# efr32_general.net
KiCad netlist of a schematic drawn in Altium Designer
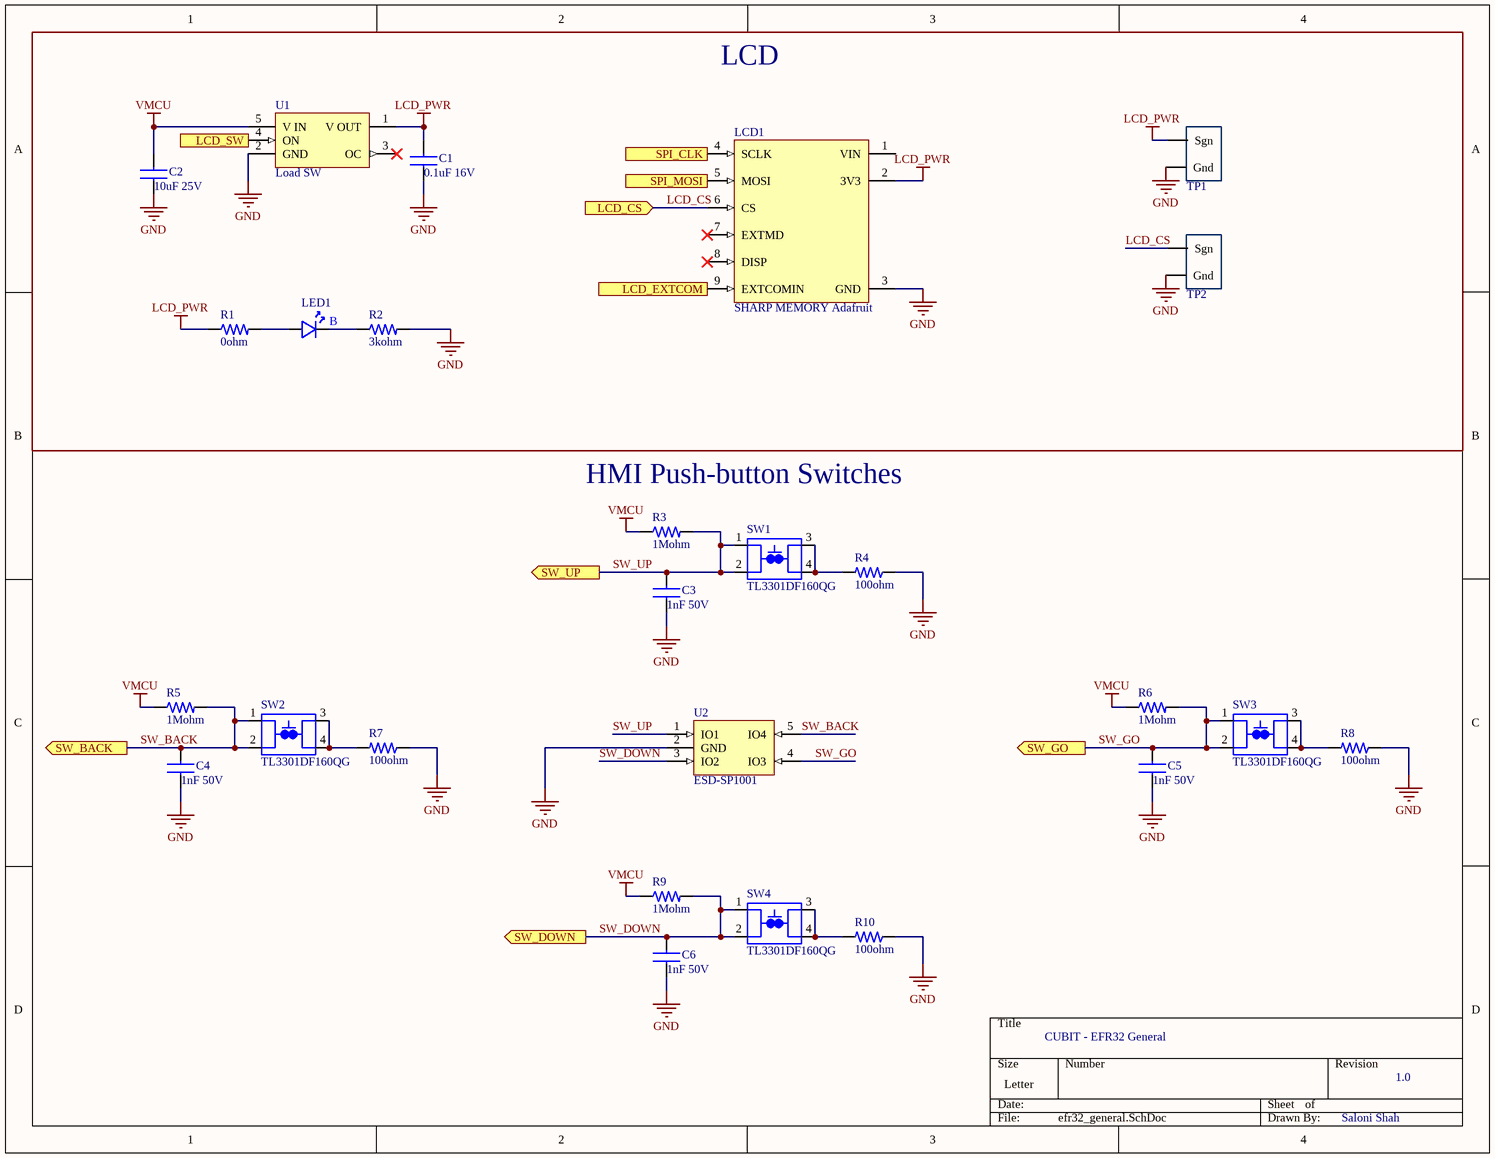
[diagram p0: efr32_general.SchDoc]

(export (version "E")
  (design (tool "Eeschema 10.0.6"))
  (components
    (comp (ref "C1")
      (value "0.1uF 16V")
      (footprint "CAP_0805_02X125")
      (description "Cap Ceramic 0.1uF 16V X7R 10% SMD 0805 125°C Paper T/R")
      (fields
        (field (name "MANUFACTURER") "KEMET")
        (field (name "MANUFACTURER PART NUMBER") "C0805C104K4RACAUTO")
      )
      (libsource (lib "LPEDT_proj_lib") (part "C0805C104K4RACAUTO"))
    )
    (comp (ref "C2")
      (value "10uF 25V")
      (footprint "CAP_0805_02X125")
      (description "Cap 0805 25 V 10 uF ±20% Tolerance X5R Monolithic Ceramic Chip Capacitor")
      (fields
        (field (name "MANUFACTURER") "Murata")
        (field (name "MANUFACTURER PART NUMBER") "GRM21BR61E106KA73K")
      )
      (libsource (lib "LPEDT_proj_lib") (part "GRM21BR61E106KA73K"))
    )
    (comp (ref "C3")
      (value "1nF 50V")
      (footprint "CAP_0805_02X125")
      (description "1nF ±10% 50V X7R 0805")
      (fields
        (field (name "MANUFACTURER") "Samsung")
        (field (name "MANUFACTURER PART NUMBER") "CL21B102KBANFNC")
      )
      (libsource (lib "LPEDT_proj_lib") (part "CL21B102KBANFNC"))
    )
    (comp (ref "C4")
      (value "1nF 50V")
      (footprint "CAP_0805_02X125")
      (description "1nF ±10% 50V X7R 0805")
      (fields
        (field (name "MANUFACTURER") "Samsung")
        (field (name "MANUFACTURER PART NUMBER") "CL21B102KBANFNC")
      )
      (libsource (lib "LPEDT_proj_lib") (part "CL21B102KBANFNC"))
    )
    (comp (ref "C5")
      (value "1nF 50V")
      (footprint "CAP_0805_02X125")
      (description "1nF ±10% 50V X7R 0805")
      (fields
        (field (name "MANUFACTURER") "Samsung")
        (field (name "MANUFACTURER PART NUMBER") "CL21B102KBANFNC")
      )
      (libsource (lib "LPEDT_proj_lib") (part "CL21B102KBANFNC"))
    )
    (comp (ref "C6")
      (value "1nF 50V")
      (footprint "CAP_0805_02X125")
      (description "1nF ±10% 50V X7R 0805")
      (fields
        (field (name "MANUFACTURER") "Samsung")
        (field (name "MANUFACTURER PART NUMBER") "CL21B102KBANFNC")
      )
      (libsource (lib "LPEDT_proj_lib") (part "CL21B102KBANFNC"))
    )
    (comp (ref "LCD1")
      (value "SHARP MEMORY Adafruit")
      (footprint "LCD_SHARP_MEMORY_9_PIN")
      (description "Conn AV RCA (Phono) Plug 2 Cont Sz 0.125\" Cbl Mnt Clamp Copper Alloy")
      (fields
        (field (name "MANUFACTURER") "Adafruit Industries")
        (field (name "MANUFACTURER PART NUMBER") "3502")
      )
      (libsource (lib "LPEDT_proj_lib") (part "3502"))
    )
    (comp (ref "LED1")
      (value "150060BS75000")
      (footprint "LED_0603_RED_WL-SMCW")
      (description "Led, Blue, 470 Nm, 3.2 V, 30 Ma, 145 Mcd Rohs Compliant: Yes")
      (fields (field (name "MANUFACTURER") "Wurth Electronics"))
      (libsource (lib "LPEDT_proj_lib") (part "150060BS75000"))
    )
    (comp (ref "R1")
      (value "0ohm")
      (footprint "CAP_0402_1mm")
      (description "Res 0 Ohms ±5% 0.063 W 0402 Thick Film Surface Mount Chip Resistor")
      (fields
        (field (name "MANUFACTURER") "Samsung")
        (field (name "MANUFACTURER PART NUMBER") "RC1005J000CS")
      )
      (libsource (lib "LPEDT_proj_lib") (part "RC1005J000CS"))
    )
    (comp (ref "R2")
      (value "3kohm")
      (footprint "CAP_0603_1MM")
      (description "Res 3000Ω ± 1.00% 0.1W ± 100ppm/℃ 0603")
      (fields
        (field (name "MANUFACTURER") "Yageo")
        (field (name "MANUFACTURER PART NUMBER") "RC0603FR-073KL")
      )
      (libsource (lib "LPEDT_proj_lib") (part "RC0603FR-073KL"))
    )
    (comp (ref "R3")
      (value "1Mohm")
      (footprint "2_Chip_0603_RMCF")
      (description "Res 1M Ohm 1% 1/10W ±100ppm/°C Molded SMD Paper T/R")
      (fields
        (field (name "MANUFACTURER") "Stackpole Electronics")
        (field (name "MANUFACTURER PART NUMBER") "RMCF0603FT1M00")
      )
      (libsource (lib "LPEDT_proj_lib") (part "RMCF0603FT1M00"))
    )
    (comp (ref "R4")
      (value "100ohm")
      (footprint "2_Chip_0603_RMCF")
      (description "Res 100 Ohm 1% 1/10W ±100ppm/°C Molded SMD SMD Paper T/R")
      (fields
        (field (name "MANUFACTURER") "Stackpole Electronics")
        (field (name "MANUFACTURER PART NUMBER") "RMCF0603FT100R")
      )
      (libsource (lib "LPEDT_proj_lib") (part "RMCF0603FT100R"))
    )
    (comp (ref "R5")
      (value "1Mohm")
      (footprint "2_Chip_0603_RMCF")
      (description "Res 1M Ohm 1% 1/10W ±100ppm/°C Molded SMD Paper T/R")
      (fields
        (field (name "MANUFACTURER") "Stackpole Electronics")
        (field (name "MANUFACTURER PART NUMBER") "RMCF0603FT1M00")
      )
      (libsource (lib "LPEDT_proj_lib") (part "RMCF0603FT1M00"))
    )
    (comp (ref "R6")
      (value "1Mohm")
      (footprint "2_Chip_0603_RMCF")
      (description "Res 1M Ohm 1% 1/10W ±100ppm/°C Molded SMD Paper T/R")
      (fields
        (field (name "MANUFACTURER") "Stackpole Electronics")
        (field (name "MANUFACTURER PART NUMBER") "RMCF0603FT1M00")
      )
      (libsource (lib "LPEDT_proj_lib") (part "RMCF0603FT1M00"))
    )
    (comp (ref "R7")
      (value "100ohm")
      (footprint "2_Chip_0603_RMCF")
      (description "Res 100 Ohm 1% 1/10W ±100ppm/°C Molded SMD SMD Paper T/R")
      (fields
        (field (name "MANUFACTURER") "Stackpole Electronics")
        (field (name "MANUFACTURER PART NUMBER") "RMCF0603FT100R")
      )
      (libsource (lib "LPEDT_proj_lib") (part "RMCF0603FT100R"))
    )
    (comp (ref "R8")
      (value "100ohm")
      (footprint "2_Chip_0603_RMCF")
      (description "Res 100 Ohm 1% 1/10W ±100ppm/°C Molded SMD SMD Paper T/R")
      (fields
        (field (name "MANUFACTURER") "Stackpole Electronics")
        (field (name "MANUFACTURER PART NUMBER") "RMCF0603FT100R")
      )
      (libsource (lib "LPEDT_proj_lib") (part "RMCF0603FT100R"))
    )
    (comp (ref "R9")
      (value "1Mohm")
      (footprint "2_Chip_0603_RMCF")
      (description "Res 1M Ohm 1% 1/10W ±100ppm/°C Molded SMD Paper T/R")
      (fields
        (field (name "MANUFACTURER") "Stackpole Electronics")
        (field (name "MANUFACTURER PART NUMBER") "RMCF0603FT1M00")
      )
      (libsource (lib "LPEDT_proj_lib") (part "RMCF0603FT1M00"))
    )
    (comp (ref "R10")
      (value "100ohm")
      (footprint "2_Chip_0603_RMCF")
      (description "Res 100 Ohm 1% 1/10W ±100ppm/°C Molded SMD SMD Paper T/R")
      (fields
        (field (name "MANUFACTURER") "Stackpole Electronics")
        (field (name "MANUFACTURER PART NUMBER") "RMCF0603FT100R")
      )
      (libsource (lib "LPEDT_proj_lib") (part "RMCF0603FT100R"))
    )
    (comp (ref "SW1")
      (value "TL3301DF160QG")
      (footprint "SW_TL3301DF160QG")
      (description "Tactile Switch SPST-NO Top Actuated Surface Mount")
      (fields (field (name "MF") "E-Switch"))
      (libsource (lib "LPEDT_proj_lib") (part "TL3301DF160QG"))
    )
    (comp (ref "SW2")
      (value "TL3301DF160QG")
      (footprint "SW_TL3301DF160QG")
      (description "Tactile Switch SPST-NO Top Actuated Surface Mount")
      (fields (field (name "MF") "E-Switch"))
      (libsource (lib "LPEDT_proj_lib") (part "TL3301DF160QG"))
    )
    (comp (ref "SW3")
      (value "TL3301DF160QG")
      (footprint "SW_TL3301DF160QG")
      (description "Tactile Switch SPST-NO Top Actuated Surface Mount")
      (fields (field (name "MF") "E-Switch"))
      (libsource (lib "LPEDT_proj_lib") (part "TL3301DF160QG"))
    )
    (comp (ref "SW4")
      (value "TL3301DF160QG")
      (footprint "SW_TL3301DF160QG")
      (description "Tactile Switch SPST-NO Top Actuated Surface Mount")
      (fields (field (name "MF") "E-Switch"))
      (libsource (lib "LPEDT_proj_lib") (part "TL3301DF160QG"))
    )
    (comp (ref "TP1")
      (value "10x Probe TP")
      (footprint "TP10x_Probe")
      (description "Test Point 300 mil centers")
      (libsource (lib "LPEDT_proj_lib") (part "TP_10x_Probe"))
    )
    (comp (ref "TP2")
      (value "10x Probe TP")
      (footprint "TP10x_Probe")
      (description "Test Point 300 mil centers")
      (libsource (lib "LPEDT_proj_lib") (part "TP_10x_Probe"))
    )
    (comp (ref "U1")
      (value "Load SW")
      (footprint "SOT65P210X110-5N")
      (description "5.5-V, 0.1-A, 500-mΩ, load switch with current limit and active low enable 5-SC70 -40 to 85")
      (fields
        (field (name "MANUFACTURER") "Texas Instruments")
        (field (name "MANUFACTURER PART NUMBER") "TPS22942DCKR")
      )
      (libsource (lib "LPEDT_proj_lib") (part "TPS22942DCKR"))
    )
    (comp (ref "U2")
      (value "ESD-SP1001")
      (footprint "SOT65P210X110-5N")
      (description "TVS DIODE 5.5VWM 13VC SC70-5")
      (fields
        (field (name "MANUFACTURER") "Littelfuse")
        (field (name "MANUFACTURER PART NUMBER") "SP1001-04JTG")
      )
      (libsource (lib "LPEDT_proj_lib") (part "SP1001-04JTG"))
    )
  )
  (nets
    (net (code "1") (name "/LCD_CS") (class "Default")
      (node (ref "LCD1") (pin "6") (pinfunction "CS_6") (pintype "input"))
      (node (ref "TP2") (pin "1") (pinfunction "Sgn_1") (pintype "passive"))
    )
    (net (code "2") (name "/LCD_EXTCOM") (class "Default")
      (node (ref "LCD1") (pin "9") (pinfunction "EXTCOMIN_9") (pintype "input"))
    )
    (net (code "3") (name "/LCD_SW") (class "Default")
      (node (ref "U1") (pin "4") (pinfunction "ON_4") (pintype "input"))
    )
    (net (code "4") (name "/SPI_CLK") (class "Default")
      (node (ref "LCD1") (pin "4") (pinfunction "SCLK_4") (pintype "input"))
    )
    (net (code "5") (name "/SPI_MOSI") (class "Default")
      (node (ref "LCD1") (pin "5") (pinfunction "MOSI_5") (pintype "input"))
    )
    (net (code "6") (name "/SW_BACK") (class "Default")
      (node (ref "C4") (pin "1") (pinfunction "1_1") (pintype "passive"))
      (node (ref "R5") (pin "2") (pinfunction "2_2") (pintype "passive"))
      (node (ref "SW2") (pin "1") (pinfunction "1_1") (pintype "passive"))
      (node (ref "SW2") (pin "2") (pinfunction "2_2") (pintype "passive"))
      (node (ref "U2") (pin "5") (pinfunction "IO4_5") (pintype "input"))
    )
    (net (code "7") (name "/SW_DOWN") (class "Default")
      (node (ref "C6") (pin "1") (pinfunction "1_1") (pintype "passive"))
      (node (ref "R9") (pin "2") (pinfunction "2_2") (pintype "passive"))
      (node (ref "SW4") (pin "1") (pinfunction "1_1") (pintype "passive"))
      (node (ref "SW4") (pin "2") (pinfunction "2_2") (pintype "passive"))
      (node (ref "U2") (pin "3") (pinfunction "IO2_3") (pintype "input"))
    )
    (net (code "8") (name "/SW_GO") (class "Default")
      (node (ref "C5") (pin "1") (pinfunction "1_1") (pintype "passive"))
      (node (ref "R6") (pin "2") (pinfunction "2_2") (pintype "passive"))
      (node (ref "SW3") (pin "1") (pinfunction "1_1") (pintype "passive"))
      (node (ref "SW3") (pin "2") (pinfunction "2_2") (pintype "passive"))
      (node (ref "U2") (pin "4") (pinfunction "IO3_4") (pintype "input"))
    )
    (net (code "9") (name "/SW_UP") (class "Default")
      (node (ref "C3") (pin "1") (pinfunction "1_1") (pintype "passive"))
      (node (ref "R3") (pin "2") (pinfunction "2_2") (pintype "passive"))
      (node (ref "SW1") (pin "1") (pinfunction "1_1") (pintype "passive"))
      (node (ref "SW1") (pin "2") (pinfunction "2_2") (pintype "passive"))
      (node (ref "U2") (pin "1") (pinfunction "IO1_1") (pintype "input"))
    )
    (net (code "10") (name "GND") (class "Default")
      (node (ref "C1") (pin "2") (pinfunction "2_2") (pintype "passive"))
      (node (ref "C2") (pin "2") (pinfunction "2_2") (pintype "passive"))
      (node (ref "C3") (pin "2") (pinfunction "2_2") (pintype "passive"))
      (node (ref "C4") (pin "2") (pinfunction "2_2") (pintype "passive"))
      (node (ref "C5") (pin "2") (pinfunction "2_2") (pintype "passive"))
      (node (ref "C6") (pin "2") (pinfunction "2_2") (pintype "passive"))
      (node (ref "LCD1") (pin "3") (pinfunction "GND_3") (pintype "power_in"))
      (node (ref "R10") (pin "1") (pinfunction "1_1") (pintype "passive"))
      (node (ref "R2") (pin "2") (pinfunction "2_2") (pintype "passive"))
      (node (ref "R4") (pin "1") (pinfunction "1_1") (pintype "passive"))
      (node (ref "R7") (pin "1") (pinfunction "1_1") (pintype "passive"))
      (node (ref "R8") (pin "1") (pinfunction "1_1") (pintype "passive"))
      (node (ref "TP1") (pin "2") (pinfunction "Gnd_2") (pintype "passive"))
      (node (ref "TP2") (pin "2") (pinfunction "Gnd_2") (pintype "passive"))
      (node (ref "U1") (pin "2") (pinfunction "GND_2") (pintype "power_in"))
      (node (ref "U2") (pin "2") (pinfunction "GND_2") (pintype "power_in"))
    )
    (net (code "11") (name "LCD_PWR") (class "Default")
      (node (ref "C1") (pin "1") (pinfunction "1_1") (pintype "passive"))
      (node (ref "LCD1") (pin "2") (pinfunction "3V3_2") (pintype "power_in"))
      (node (ref "R1") (pin "1") (pinfunction "1_1") (pintype "passive"))
      (node (ref "TP1") (pin "1") (pinfunction "Sgn_1") (pintype "passive"))
      (node (ref "U1") (pin "1") (pinfunction "V_OUT_1") (pintype "power_in"))
    )
    (net (code "12") (name "Net-(LED1-PadA)") (class "Default")
      (node (ref "LED1") (pin "A") (pinfunction "A_A") (pintype "passive"))
      (node (ref "R1") (pin "2") (pinfunction "2_2") (pintype "passive"))
    )
    (net (code "13") (name "Net-(LED1-PadC)") (class "Default")
      (node (ref "LED1") (pin "C") (pinfunction "C_C") (pintype "passive"))
      (node (ref "R2") (pin "1") (pinfunction "1_1") (pintype "passive"))
    )
    (net (code "14") (name "Net-(R4-Pad2)") (class "Default")
      (node (ref "R4") (pin "2") (pinfunction "2_2") (pintype "passive"))
      (node (ref "SW1") (pin "3") (pinfunction "3_3") (pintype "passive"))
      (node (ref "SW1") (pin "4") (pinfunction "4_4") (pintype "passive"))
    )
    (net (code "15") (name "Net-(R7-Pad2)") (class "Default")
      (node (ref "R7") (pin "2") (pinfunction "2_2") (pintype "passive"))
      (node (ref "SW2") (pin "3") (pinfunction "3_3") (pintype "passive"))
      (node (ref "SW2") (pin "4") (pinfunction "4_4") (pintype "passive"))
    )
    (net (code "16") (name "Net-(R8-Pad2)") (class "Default")
      (node (ref "R8") (pin "2") (pinfunction "2_2") (pintype "passive"))
      (node (ref "SW3") (pin "3") (pinfunction "3_3") (pintype "passive"))
      (node (ref "SW3") (pin "4") (pinfunction "4_4") (pintype "passive"))
    )
    (net (code "17") (name "Net-(R10-Pad2)") (class "Default")
      (node (ref "R10") (pin "2") (pinfunction "2_2") (pintype "passive"))
      (node (ref "SW4") (pin "3") (pinfunction "3_3") (pintype "passive"))
      (node (ref "SW4") (pin "4") (pinfunction "4_4") (pintype "passive"))
    )
    (net (code "18") (name "VMCU") (class "Default")
      (node (ref "C2") (pin "1") (pinfunction "1_1") (pintype "passive"))
      (node (ref "R3") (pin "1") (pinfunction "1_1") (pintype "passive"))
      (node (ref "R5") (pin "1") (pinfunction "1_1") (pintype "passive"))
      (node (ref "R6") (pin "1") (pinfunction "1_1") (pintype "passive"))
      (node (ref "R9") (pin "1") (pinfunction "1_1") (pintype "passive"))
      (node (ref "U1") (pin "5") (pinfunction "V_IN_5") (pintype "power_in"))
    )
    (net (code "19") (name "unconnected-(LCD1-DISP-Pad8)") (class "Default")
      (node (ref "LCD1") (pin "8") (pinfunction "DISP_8") (pintype "input+no_connect"))
    )
    (net (code "20") (name "unconnected-(LCD1-EXTMD-Pad7)") (class "Default")
      (node (ref "LCD1") (pin "7") (pinfunction "EXTMD_7") (pintype "input+no_connect"))
    )
    (net (code "21") (name "unconnected-(LCD1-VIN-Pad1)") (class "Default")
      (node (ref "LCD1") (pin "1") (pinfunction "VIN_1") (pintype "power_in"))
    )
    (net (code "22") (name "unconnected-(U1-OC-Pad3)") (class "Default")
      (node (ref "U1") (pin "3") (pinfunction "OC_3") (pintype "output+no_connect"))
    )
  )
)
